# Pure_SH.net
KiCad netlist of a schematic drawn in EAGLE
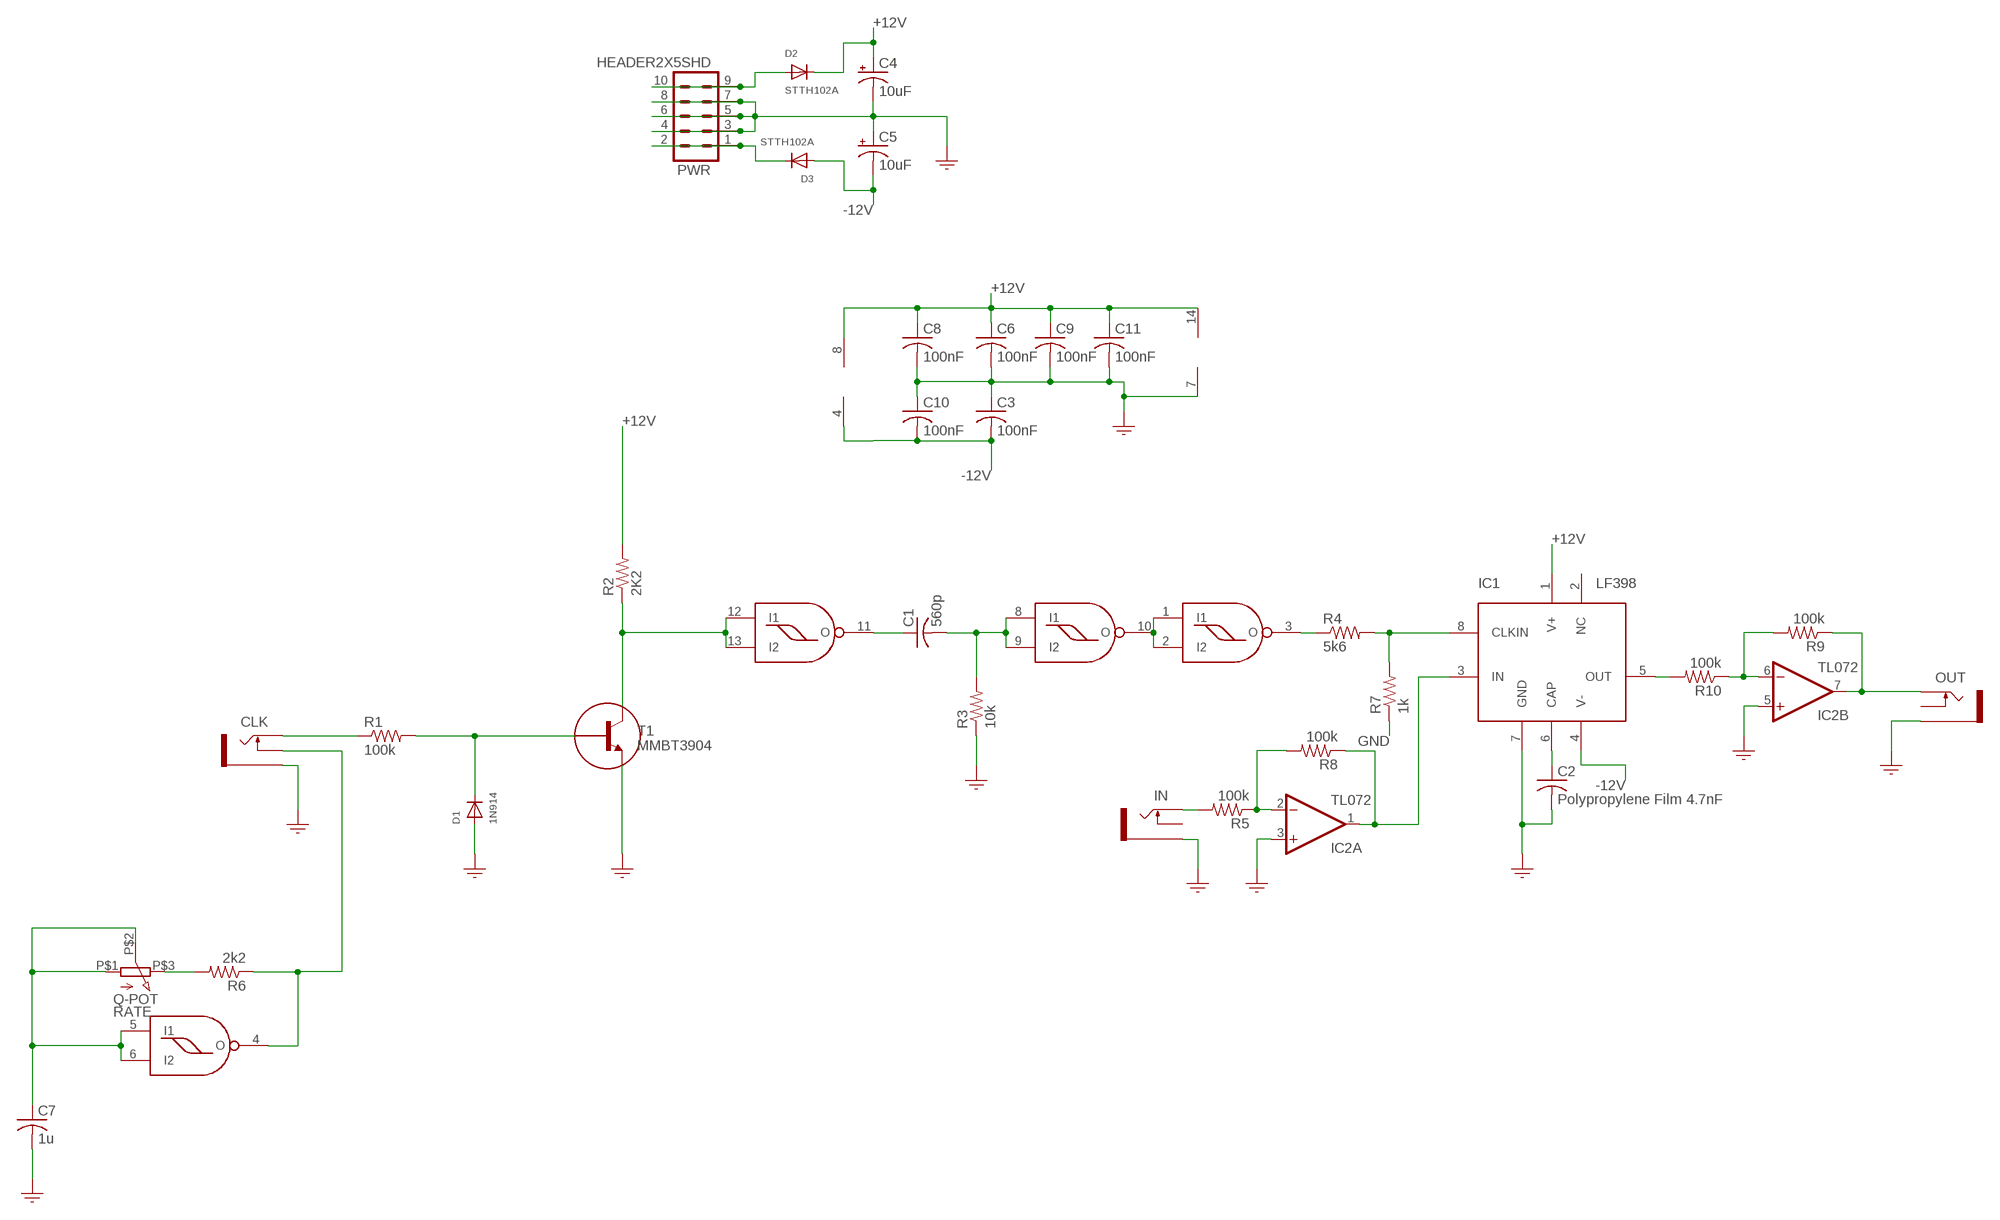
[diagram p0: schematic, sheet 1]

(export (version "E")
  (design (tool "Eeschema 10.0.6"))
  (components
    (comp (ref "C1")
      (value "560p")
      (footprint "eagle-import:C0805")
      (libsource (lib "eagle-import") (part "CAPACITOR-USC0805"))
    )
    (comp (ref "C2")
      (value "Polypropylene Film 4.7nF")
      (footprint "eagle-import:C050-045X075")
      (libsource (lib "eagle-import") (part "CAPACITOR-US050-045X075"))
    )
    (comp (ref "C3")
      (value "100nF")
      (footprint "eagle-import:C0805")
      (libsource (lib "eagle-import") (part "CAPACITOR-USC0805"))
    )
    (comp (ref "C4")
      (value "10uF")
      (footprint "eagle-import:153CLV-0505")
      (libsource (lib "eagle-import") (part "CAPACITOR_POL-US153CLV-0505"))
    )
    (comp (ref "C5")
      (value "10uF")
      (footprint "eagle-import:153CLV-0505")
      (libsource (lib "eagle-import") (part "CAPACITOR_POL-US153CLV-0505"))
    )
    (comp (ref "C6")
      (value "100nF")
      (footprint "eagle-import:C0805")
      (libsource (lib "eagle-import") (part "CAPACITOR-USC0805"))
    )
    (comp (ref "C7")
      (value "1u")
      (footprint "eagle-import:C0805")
      (libsource (lib "eagle-import") (part "CAPACITOR-USC0805"))
    )
    (comp (ref "C8")
      (value "100nF")
      (footprint "eagle-import:C0805")
      (libsource (lib "eagle-import") (part "CAPACITOR-USC0805"))
    )
    (comp (ref "C9")
      (value "100nF")
      (footprint "eagle-import:C0805")
      (libsource (lib "eagle-import") (part "CAPACITOR-USC0805"))
    )
    (comp (ref "C10")
      (value "100nF")
      (footprint "eagle-import:C0805")
      (libsource (lib "eagle-import") (part "CAPACITOR-USC0805"))
    )
    (comp (ref "C11")
      (value "100nF")
      (footprint "eagle-import:C0805")
      (libsource (lib "eagle-import") (part "CAPACITOR-USC0805"))
    )
    (comp (ref "CLK")
      (value "PJ301M-12")
      (footprint "eagle-import:PJ301M-12")
      (libsource (lib "eagle-import") (part "SOCKET_MONO_3.5MMPJ301M-12"))
    )
    (comp (ref "D1")
      (value "1N914")
      (footprint "eagle-import:DO-41")
      (libsource (lib "eagle-import") (part "DIODEDO-41"))
    )
    (comp (ref "D2")
      (value "STTH102A")
      (footprint "eagle-import:DO-41")
      (libsource (lib "eagle-import") (part "DIODEDO-41"))
    )
    (comp (ref "D3")
      (value "STTH102A")
      (footprint "eagle-import:DO-41")
      (libsource (lib "eagle-import") (part "DIODEDO-41"))
    )
    (comp (ref "IC1")
      (value "LF398")
      (footprint "eagle-import:SOIC--8")
      (libsource (lib "eagle-import") (part "SAMPLE_HOLD_LF398"))
    )
    (comp (ref "IC2")
      (value "TL072")
      (footprint "eagle-import:SO08")
      (libsource (lib "eagle-import") (part "OPAMP_DUALD"))
    )
    (comp (ref "IC3")
      (value "cd4093")
      (footprint "eagle-import:SOIC14")
      (libsource (lib "eagle-import") (part "SCHMITT_TRIG_QUAD"))
    )
    (comp (ref "IN")
      (value "PJ301M-12")
      (footprint "eagle-import:PJ301M-12")
      (libsource (lib "eagle-import") (part "SOCKET_MONO_3.5MMPJ301M-12"))
    )
    (comp (ref "OUT")
      (value "PJ301M-12")
      (footprint "eagle-import:PJ301M-12")
      (libsource (lib "eagle-import") (part "SOCKET_MONO_3.5MMPJ301M-12"))
    )
    (comp (ref "PWR")
      (value "HEADER2X5SHD")
      (footprint "eagle-import:2X5-SHROUDED")
      (libsource (lib "eagle-import") (part "HEADER2X5SHD"))
    )
    (comp (ref "R1")
      (value "100k")
      (footprint "eagle-import:R0805")
      (libsource (lib "eagle-import") (part "RESISTOR_USR0805"))
    )
    (comp (ref "R2")
      (value "2K2")
      (footprint "eagle-import:R0805")
      (libsource (lib "eagle-import") (part "RESISTOR_USR0805"))
    )
    (comp (ref "R3")
      (value "10k")
      (footprint "eagle-import:R0805")
      (libsource (lib "eagle-import") (part "RESISTOR_USR0805"))
    )
    (comp (ref "R4")
      (value "5k6")
      (footprint "eagle-import:R0805")
      (libsource (lib "eagle-import") (part "RESISTOR_USR0805"))
    )
    (comp (ref "R5")
      (value "100k")
      (footprint "eagle-import:R0805")
      (libsource (lib "eagle-import") (part "RESISTOR_USR0805"))
    )
    (comp (ref "R6")
      (value "2k2")
      (footprint "eagle-import:R0805")
      (libsource (lib "eagle-import") (part "RESISTOR_USR0805"))
    )
    (comp (ref "R7")
      (value "1k")
      (footprint "eagle-import:R0805")
      (libsource (lib "eagle-import") (part "RESISTOR_USR0805"))
    )
    (comp (ref "R8")
      (value "100k")
      (footprint "eagle-import:R0805")
      (libsource (lib "eagle-import") (part "RESISTOR_USR0805"))
    )
    (comp (ref "R9")
      (value "100k")
      (footprint "eagle-import:R0805")
      (libsource (lib "eagle-import") (part "RESISTOR_USR0805"))
    )
    (comp (ref "R10")
      (value "100k")
      (footprint "eagle-import:R0805")
      (libsource (lib "eagle-import") (part "RESISTOR_USR0805"))
    )
    (comp (ref "RATE")
      (value "Q-POT")
      (footprint "eagle-import:POTENTIOMETER_9MM")
      (libsource (lib "eagle-import") (part "RESISTOR_VARIABLE9MM_POT"))
    )
    (comp (ref "T1")
      (value "MMBT3904")
      (footprint "eagle-import:SOT23")
      (libsource (lib "eagle-import") (part "TRANSISTOR_NPNSOT23"))
    )
  )
  (nets
    (net (code "1") (name "/+12V") (class "Default")
      (node (ref "C11") (pin "1") (pinfunction "1_1") (pintype "passive"))
      (node (ref "C4") (pin "+") (pinfunction "+_+") (pintype "passive"))
      (node (ref "C6") (pin "1") (pinfunction "1_1") (pintype "passive"))
      (node (ref "C8") (pin "1") (pinfunction "1_1") (pintype "passive"))
      (node (ref "C9") (pin "1") (pinfunction "1_1") (pintype "passive"))
      (node (ref "D2") (pin "C") (pinfunction "C_C") (pintype "passive"))
      (node (ref "IC1") (pin "1") (pinfunction "V+_1") (pintype "bidirectional"))
      (node (ref "IC2") (pin "8") (pinfunction "V+_8") (pintype "power_in"))
      (node (ref "IC3") (pin "14") (pinfunction "V+_14") (pintype "power_in"))
      (node (ref "R2") (pin "2") (pinfunction "2_2") (pintype "passive"))
    )
    (net (code "2") (name "/-12V") (class "Default")
      (node (ref "C10") (pin "2") (pinfunction "2_2") (pintype "passive"))
      (node (ref "C3") (pin "2") (pinfunction "2_2") (pintype "passive"))
      (node (ref "C5") (pin "-") (pinfunction "-_-") (pintype "passive"))
      (node (ref "D3") (pin "A") (pinfunction "A_A") (pintype "passive"))
      (node (ref "IC1") (pin "4") (pinfunction "V-_4") (pintype "bidirectional"))
      (node (ref "IC2") (pin "4") (pinfunction "V-_4") (pintype "power_in"))
    )
    (net (code "3") (name "GND") (class "Default")
      (node (ref "C10") (pin "1") (pinfunction "1_1") (pintype "passive"))
      (node (ref "C11") (pin "2") (pinfunction "2_2") (pintype "passive"))
      (node (ref "C2") (pin "2") (pinfunction "2_2") (pintype "passive"))
      (node (ref "C3") (pin "1") (pinfunction "1_1") (pintype "passive"))
      (node (ref "C4") (pin "-") (pinfunction "-_-") (pintype "passive"))
      (node (ref "C5") (pin "+") (pinfunction "+_+") (pintype "passive"))
      (node (ref "C6") (pin "2") (pinfunction "2_2") (pintype "passive"))
      (node (ref "C7") (pin "2") (pinfunction "2_2") (pintype "passive"))
      (node (ref "C8") (pin "2") (pinfunction "2_2") (pintype "passive"))
      (node (ref "C9") (pin "2") (pinfunction "2_2") (pintype "passive"))
      (node (ref "CLK") (pin "GND") (pinfunction "SLEEVE_GND") (pintype "passive"))
      (node (ref "D1") (pin "A") (pinfunction "A_A") (pintype "passive"))
      (node (ref "IC1") (pin "7") (pinfunction "GND_7") (pintype "bidirectional"))
      (node (ref "IC2") (pin "3") (pinfunction "+IN_3") (pintype "input"))
      (node (ref "IC2") (pin "5") (pinfunction "+IN_5") (pintype "input"))
      (node (ref "IC3") (pin "7") (pinfunction "V-_7") (pintype "power_in"))
      (node (ref "IN") (pin "GND") (pinfunction "SLEEVE_GND") (pintype "passive"))
      (node (ref "OUT") (pin "GND") (pinfunction "SLEEVE_GND") (pintype "passive"))
      (node (ref "PWR") (pin "3") (pinfunction "3_3") (pintype "passive"))
      (node (ref "PWR") (pin "4") (pinfunction "4_4") (pintype "passive"))
      (node (ref "PWR") (pin "5") (pinfunction "5_5") (pintype "passive"))
      (node (ref "PWR") (pin "6") (pinfunction "6_6") (pintype "passive"))
      (node (ref "PWR") (pin "7") (pinfunction "7_7") (pintype "passive"))
      (node (ref "PWR") (pin "8") (pinfunction "8_8") (pintype "passive"))
      (node (ref "R3") (pin "1") (pinfunction "1_1") (pintype "passive"))
      (node (ref "R7") (pin "1") (pinfunction "1_1") (pintype "passive"))
      (node (ref "T1") (pin "2") (pinfunction "E_2") (pintype "passive"))
    )
    (net (code "4") (name "Net-(CLK-PadTIP)") (class "Default")
      (node (ref "CLK") (pin "TIP") (pinfunction "TIP_TIP") (pintype "passive"))
      (node (ref "R1") (pin "1") (pinfunction "1_1") (pintype "passive"))
    )
    (net (code "5") (name "Net-(CLK-SWITCH)") (class "Default")
      (node (ref "CLK") (pin "NORM") (pinfunction "SWITCH_NORM") (pintype "passive"))
      (node (ref "IC3") (pin "4") (pinfunction "O_4") (pintype "bidirectional"))
      (node (ref "R6") (pin "1") (pinfunction "1_1") (pintype "passive"))
    )
    (net (code "6") (name "Net-(D2-PadA)") (class "Default")
      (node (ref "D2") (pin "A") (pinfunction "A_A") (pintype "passive"))
      (node (ref "PWR") (pin "10") (pinfunction "10_10") (pintype "passive"))
      (node (ref "PWR") (pin "9") (pinfunction "9_9") (pintype "passive"))
    )
    (net (code "7") (name "Net-(D3-PadC)") (class "Default")
      (node (ref "D3") (pin "C") (pinfunction "C_C") (pintype "passive"))
      (node (ref "PWR") (pin "1") (pinfunction "1_1") (pintype "passive"))
      (node (ref "PWR") (pin "2") (pinfunction "2_2") (pintype "passive"))
    )
    (net (code "8") (name "Net-(IC1-CAP)") (class "Default")
      (node (ref "C2") (pin "1") (pinfunction "1_1") (pintype "passive"))
      (node (ref "IC1") (pin "6") (pinfunction "CAP_6") (pintype "bidirectional"))
    )
    (net (code "9") (name "Net-(IC1-CLKIN)") (class "Default")
      (node (ref "IC1") (pin "8") (pinfunction "CLKIN_8") (pintype "bidirectional"))
      (node (ref "R4") (pin "2") (pinfunction "2_2") (pintype "passive"))
      (node (ref "R7") (pin "2") (pinfunction "2_2") (pintype "passive"))
    )
    (net (code "10") (name "Net-(IC1-IN)") (class "Default")
      (node (ref "IC1") (pin "3") (pinfunction "IN_3") (pintype "bidirectional"))
      (node (ref "IC2") (pin "1") (pinfunction "OUT_1") (pintype "output"))
      (node (ref "R8") (pin "1") (pinfunction "1_1") (pintype "passive"))
    )
    (net (code "11") (name "Net-(IC1-OUT)") (class "Default")
      (node (ref "IC1") (pin "5") (pinfunction "OUT_5") (pintype "bidirectional"))
      (node (ref "R10") (pin "2") (pinfunction "2_2") (pintype "passive"))
    )
    (net (code "12") (name "Net-(IC2A--IN)") (class "Default")
      (node (ref "IC2") (pin "2") (pinfunction "-IN_2") (pintype "input"))
      (node (ref "R5") (pin "1") (pinfunction "1_1") (pintype "passive"))
      (node (ref "R8") (pin "2") (pinfunction "2_2") (pintype "passive"))
    )
    (net (code "13") (name "Net-(IC2B--IN)") (class "Default")
      (node (ref "IC2") (pin "6") (pinfunction "-IN_6") (pintype "input"))
      (node (ref "R10") (pin "1") (pinfunction "1_1") (pintype "passive"))
      (node (ref "R9") (pin "2") (pinfunction "2_2") (pintype "passive"))
    )
    (net (code "14") (name "Net-(IC2B-OUT)") (class "Default")
      (node (ref "IC2") (pin "7") (pinfunction "OUT_7") (pintype "output"))
      (node (ref "OUT") (pin "TIP") (pinfunction "TIP_TIP") (pintype "passive"))
      (node (ref "R9") (pin "1") (pinfunction "1_1") (pintype "passive"))
    )
    (net (code "15") (name "Net-(IC3B-I1)") (class "Default")
      (node (ref "IC3") (pin "1") (pinfunction "I1_1") (pintype "bidirectional"))
      (node (ref "IC3") (pin "10") (pinfunction "O_10") (pintype "bidirectional"))
      (node (ref "IC3") (pin "2") (pinfunction "I2_2") (pintype "bidirectional"))
    )
    (net (code "16") (name "Net-(IC3B-O)") (class "Default")
      (node (ref "IC3") (pin "3") (pinfunction "O_3") (pintype "bidirectional"))
      (node (ref "R4") (pin "1") (pinfunction "1_1") (pintype "passive"))
    )
    (net (code "17") (name "Net-(IC3C-I1)") (class "Default")
      (node (ref "C7") (pin "1") (pinfunction "1_1") (pintype "passive"))
      (node (ref "IC3") (pin "5") (pinfunction "I1_5") (pintype "bidirectional"))
      (node (ref "IC3") (pin "6") (pinfunction "I2_6") (pintype "bidirectional"))
      (node (ref "RATE") (pin "P$1") (pinfunction "1_P$1") (pintype "passive"))
      (node (ref "RATE") (pin "P$2") (pinfunction "2_P$2") (pintype "passive"))
    )
    (net (code "18") (name "Net-(IC3D-I1)") (class "Default")
      (node (ref "C1") (pin "2") (pinfunction "2_2") (pintype "passive"))
      (node (ref "IC3") (pin "8") (pinfunction "I1_8") (pintype "bidirectional"))
      (node (ref "IC3") (pin "9") (pinfunction "I2_9") (pintype "bidirectional"))
      (node (ref "R3") (pin "2") (pinfunction "2_2") (pintype "passive"))
    )
    (net (code "19") (name "Net-(IC3E-I1)") (class "Default")
      (node (ref "IC3") (pin "12") (pinfunction "I1_12") (pintype "bidirectional"))
      (node (ref "IC3") (pin "13") (pinfunction "I2_13") (pintype "bidirectional"))
      (node (ref "R2") (pin "1") (pinfunction "1_1") (pintype "passive"))
      (node (ref "T1") (pin "3") (pinfunction "C_3") (pintype "passive"))
    )
    (net (code "20") (name "Net-(IC3E-O)") (class "Default")
      (node (ref "C1") (pin "1") (pinfunction "1_1") (pintype "passive"))
      (node (ref "IC3") (pin "11") (pinfunction "O_11") (pintype "bidirectional"))
    )
    (net (code "21") (name "Net-(IN-PadTIP)") (class "Default")
      (node (ref "IN") (pin "TIP") (pinfunction "TIP_TIP") (pintype "passive"))
      (node (ref "R5") (pin "2") (pinfunction "2_2") (pintype "passive"))
    )
    (net (code "22") (name "Net-(RATE-3)") (class "Default")
      (node (ref "R6") (pin "2") (pinfunction "2_2") (pintype "passive"))
      (node (ref "RATE") (pin "P$3") (pinfunction "3_P$3") (pintype "passive"))
    )
    (net (code "23") (name "Net-(T1-B)") (class "Default")
      (node (ref "D1") (pin "C") (pinfunction "C_C") (pintype "passive"))
      (node (ref "R1") (pin "2") (pinfunction "2_2") (pintype "passive"))
      (node (ref "T1") (pin "1") (pinfunction "B_1") (pintype "passive"))
    )
    (net (code "24") (name "unconnected-(IC1-NC-Pad2)") (class "Default")
      (node (ref "IC1") (pin "2") (pinfunction "NC_2") (pintype "bidirectional"))
    )
    (net (code "25") (name "unconnected-(IN-SWITCH-PadNORM)") (class "Default")
      (node (ref "IN") (pin "NORM") (pinfunction "SWITCH_NORM") (pintype "passive"))
    )
    (net (code "26") (name "unconnected-(OUT-SWITCH-PadNORM)") (class "Default")
      (node (ref "OUT") (pin "NORM") (pinfunction "SWITCH_NORM") (pintype "passive"))
    )
  )
)
